# SCH_Desky_2024-12-20.net
KiCad netlist of a schematic drawn in EasyEDA
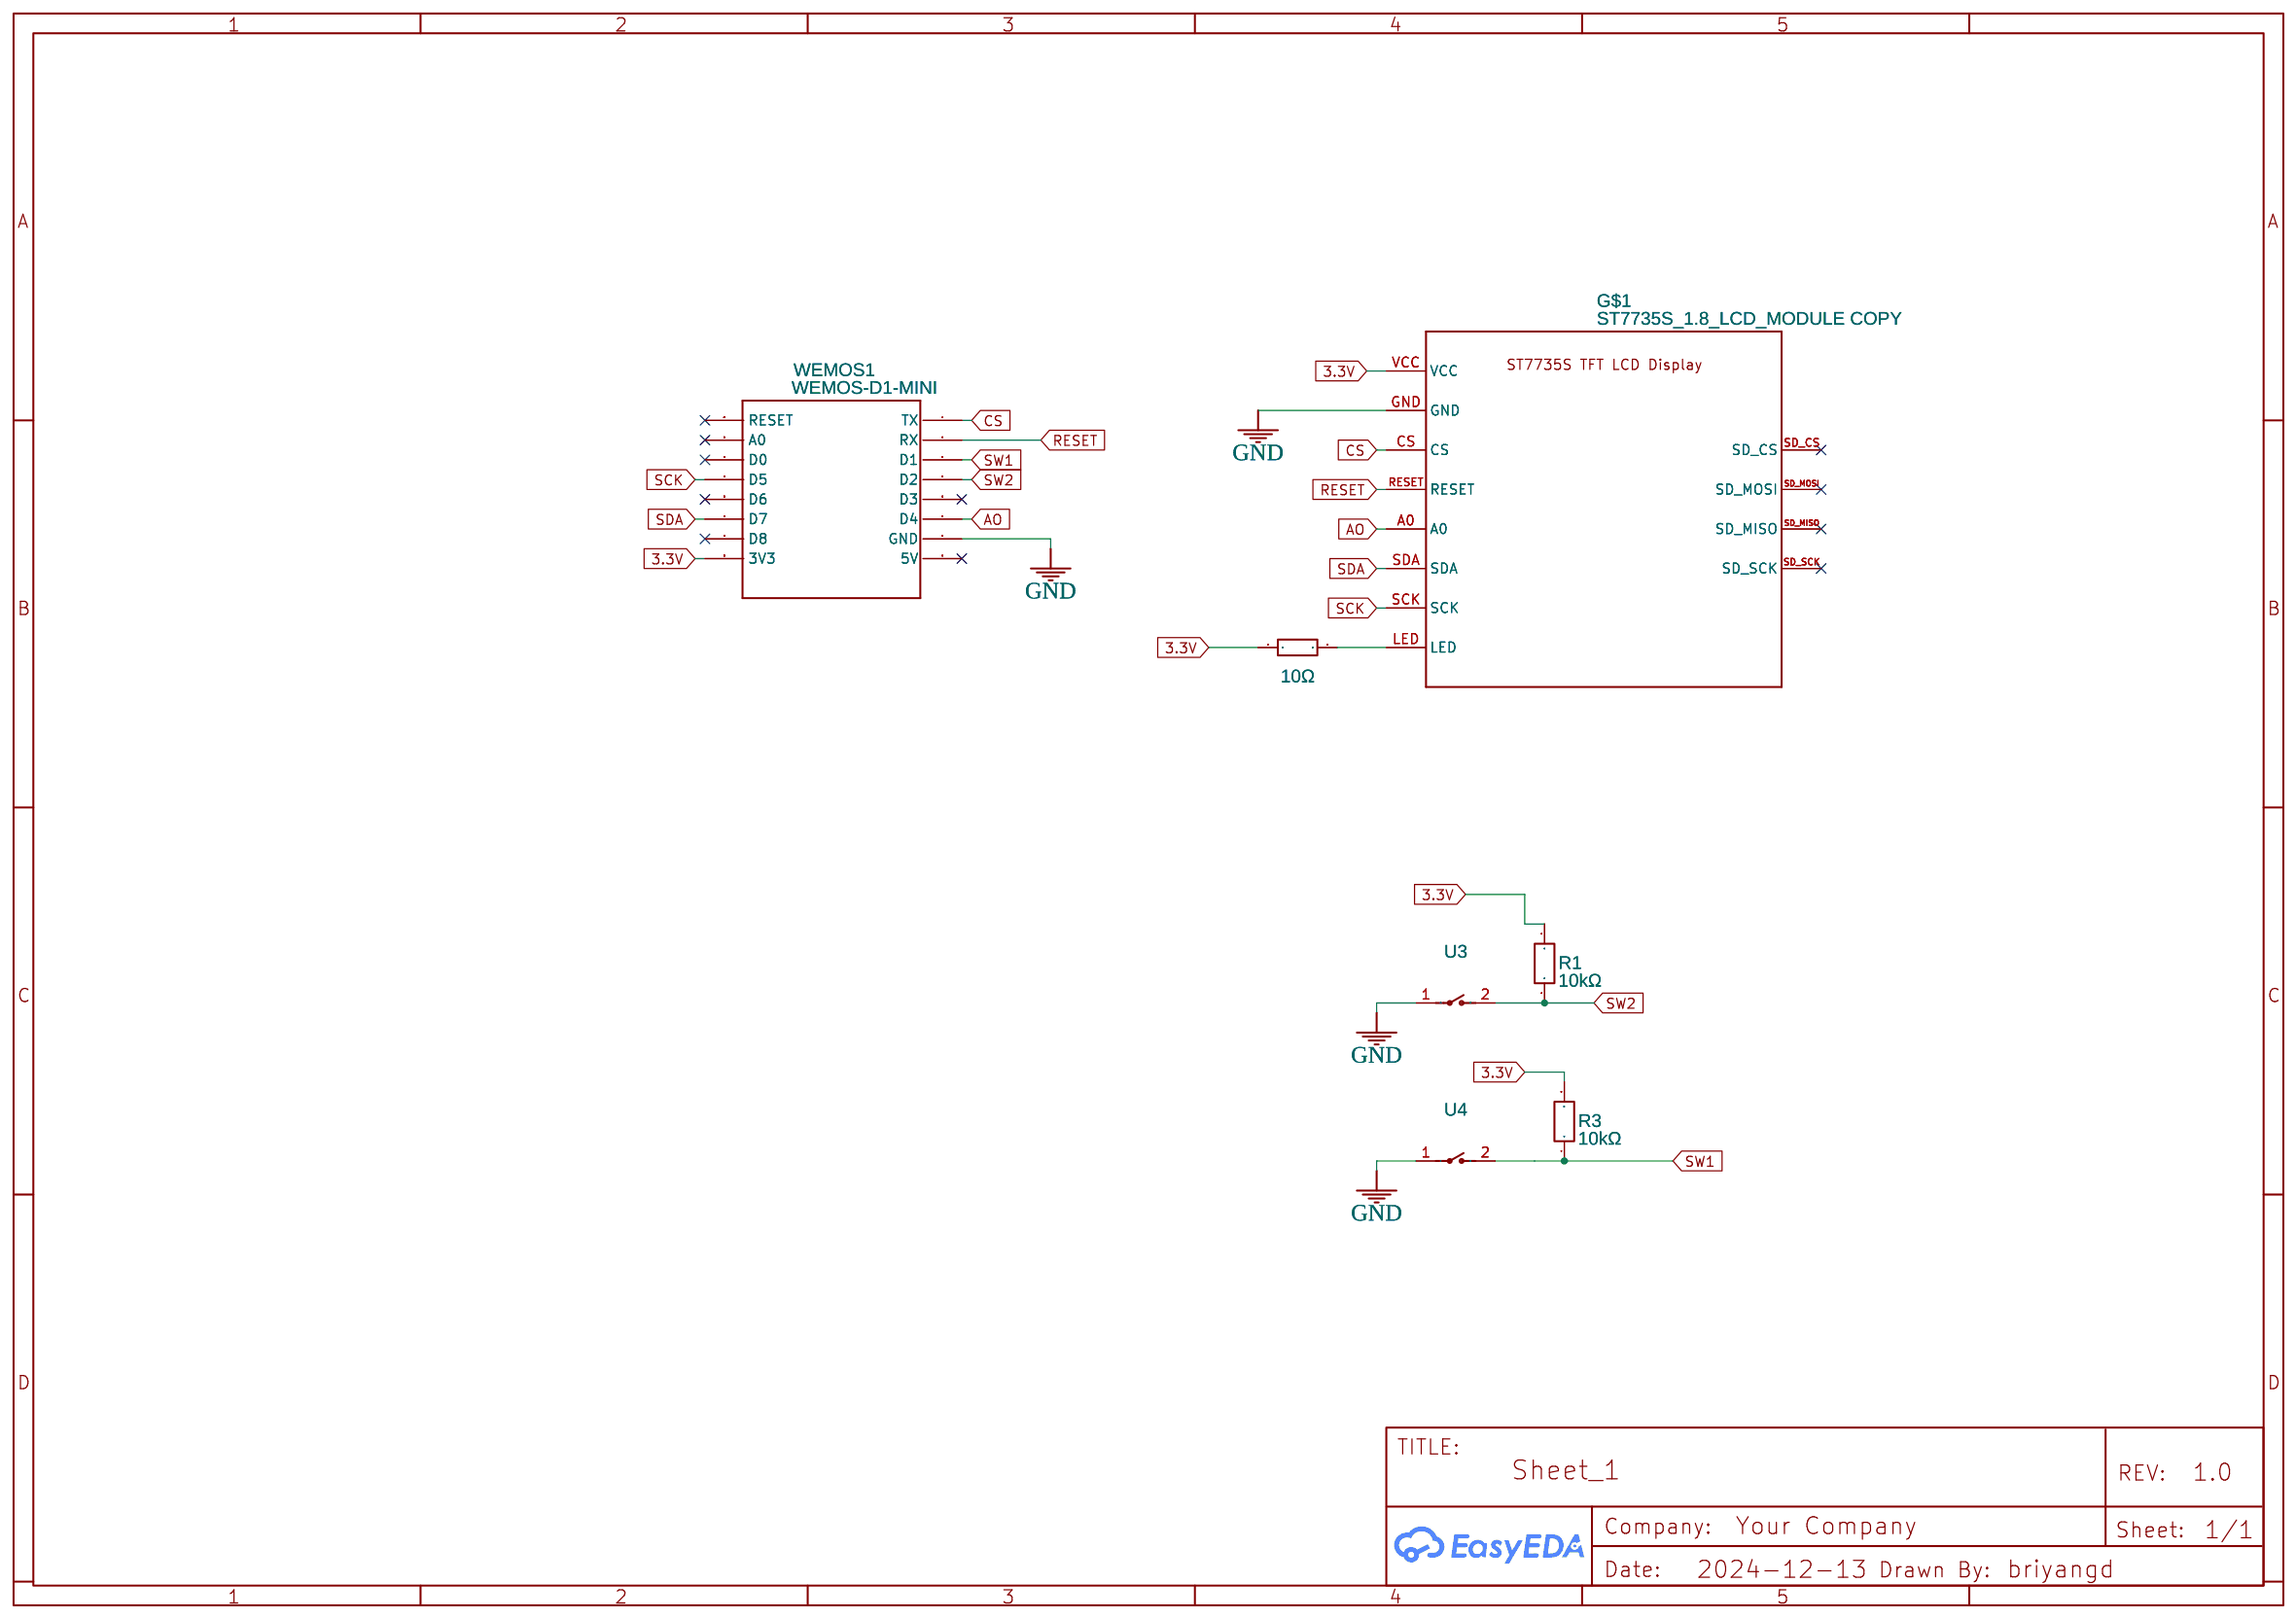
[diagram p0: schematic sheet]

(export (version "E")
  (design (tool "Eeschema 10.0.6"))
  (components
    (comp (ref "G$1")
      (value "ST7735S_1.8_LCD_MODULE COPY")
      (libsource (lib "") (part "ST7735S_1.8_LCD_MODULE COPY"))
    )
    (comp (ref "R1")
      (value "10kΩ")
      (fields
        (field (name "Manufacturer Part") "RN1/4W10KFT/BA1")
        (field (name "Manufacturer") "Tyohm(幸亚电阻)")
      )
      (libsource (lib "") (part "RN 1/4W 10K F T/B A1"))
    )
    (comp (ref "R2")
      (value "10Ω")
      (fields (field (name "Manufacturer Part") "KNP2W-10Ω±5% T") (field (name "Manufacturer") "CCO(千志电子)"))
      (libsource (lib "") (part "KNP2W-10Ω±5% T"))
    )
    (comp (ref "R3")
      (value "10kΩ")
      (fields
        (field (name "Manufacturer Part") "RN1/4W10KFT/BA1")
        (field (name "Manufacturer") "Tyohm(幸亚电阻)")
      )
      (libsource (lib "") (part "RN 1/4W 10K F T/B A1"))
    )
    (comp (ref "U3")
      (value "EVQ-11D05B")
      (fields (field (name "Manufacturer") "PANASONIC(松下)"))
      (libsource (lib "") (part "EVQ-11D05B"))
    )
    (comp (ref "U4")
      (value "EVQ-11D05B")
      (fields (field (name "Manufacturer") "PANASONIC(松下)"))
      (libsource (lib "") (part "EVQ-11D05B"))
    )
    (comp (ref "WEMOS1") (value "WEMOS-D1-MINI") (libsource (lib "") (part "WEMOS-D1-MINI")))
  )
  (nets
    (net (code "1") (name "3.3V") (class "Default")
      (node (ref "G$1") (pin "VCC") (pinfunction "VCC_VCC") (pintype "bidirectional"))
      (node (ref "R1") (pin "2") (pinfunction "2_2") (pintype "unspecified"))
      (node (ref "R2") (pin "1") (pinfunction "1_1") (pintype "unspecified"))
      (node (ref "R3") (pin "2") (pinfunction "2_2") (pintype "unspecified"))
      (node (ref "WEMOS1") (pin "3V3") (pinfunction "3V3_3V3") (pintype "bidirectional"))
    )
    (net (code "2") (name "AO") (class "Default")
      (node (ref "G$1") (pin "A0") (pinfunction "A0_A0") (pintype "bidirectional"))
      (node (ref "WEMOS1") (pin "D4") (pinfunction "D4_D4") (pintype "bidirectional"))
    )
    (net (code "3") (name "CS") (class "Default")
      (node (ref "G$1") (pin "CS") (pinfunction "CS_CS") (pintype "bidirectional"))
      (node (ref "WEMOS1") (pin "TX") (pinfunction "TX_TX") (pintype "bidirectional"))
    )
    (net (code "4") (name "GND") (class "Default")
      (node (ref "G$1") (pin "GND") (pinfunction "GND_GND") (pintype "bidirectional"))
      (node (ref "U3") (pin "1") (pinfunction "1_1") (pintype "unspecified"))
      (node (ref "U4") (pin "1") (pinfunction "1_1") (pintype "unspecified"))
      (node (ref "WEMOS1") (pin "GND") (pinfunction "GND_GND") (pintype "bidirectional"))
    )
    (net (code "5") (name "Net-(G$1-PadLED)") (class "Default")
      (node (ref "G$1") (pin "LED") (pinfunction "LED_LED") (pintype "bidirectional"))
      (node (ref "R2") (pin "2") (pinfunction "2_2") (pintype "unspecified"))
    )
    (net (code "6") (name "RESET") (class "Default")
      (node (ref "G$1") (pin "RESET") (pinfunction "RESET_RESET") (pintype "bidirectional"))
      (node (ref "WEMOS1") (pin "RX") (pinfunction "RX_RX") (pintype "bidirectional"))
    )
    (net (code "7") (name "SCK") (class "Default")
      (node (ref "G$1") (pin "SCK") (pinfunction "SCK_SCK") (pintype "bidirectional"))
      (node (ref "WEMOS1") (pin "D5") (pinfunction "D5_D5") (pintype "bidirectional"))
    )
    (net (code "8") (name "SDA") (class "Default")
      (node (ref "G$1") (pin "SDA") (pinfunction "SDA_SDA") (pintype "bidirectional"))
      (node (ref "WEMOS1") (pin "D7") (pinfunction "D7_D7") (pintype "bidirectional"))
    )
    (net (code "9") (name "SW1") (class "Default")
      (node (ref "R3") (pin "1") (pinfunction "1_1") (pintype "unspecified"))
      (node (ref "U4") (pin "2") (pinfunction "2_2") (pintype "unspecified"))
      (node (ref "WEMOS1") (pin "D1") (pinfunction "D1_D1") (pintype "bidirectional"))
    )
    (net (code "10") (name "SW2") (class "Default")
      (node (ref "R1") (pin "1") (pinfunction "1_1") (pintype "unspecified"))
      (node (ref "U3") (pin "2") (pinfunction "2_2") (pintype "unspecified"))
      (node (ref "WEMOS1") (pin "D2") (pinfunction "D2_D2") (pintype "bidirectional"))
    )
    (net (code "11") (name "unconnected-(G$1-PadSD_CS)") (class "Default")
      (node (ref "G$1") (pin "SD_CS") (pinfunction "SD_CS_SD_CS") (pintype "bidirectional+no_connect"))
    )
    (net (code "12") (name "unconnected-(G$1-PadSD_MISO)") (class "Default")
      (node (ref "G$1") (pin "SD_MISO") (pinfunction "SD_MISO_SD_MISO") (pintype "bidirectional+no_connect"))
    )
    (net (code "13") (name "unconnected-(G$1-PadSD_MOSI)") (class "Default")
      (node (ref "G$1") (pin "SD_MOSI") (pinfunction "SD_MOSI_SD_MOSI") (pintype "bidirectional+no_connect"))
    )
    (net (code "14") (name "unconnected-(G$1-PadSD_SCK)") (class "Default")
      (node (ref "G$1") (pin "SD_SCK") (pinfunction "SD_SCK_SD_SCK") (pintype "bidirectional+no_connect"))
    )
    (net (code "15") (name "unconnected-(WEMOS1-Pad5V)") (class "Default")
      (node (ref "WEMOS1") (pin "5V") (pinfunction "5V_5V") (pintype "bidirectional+no_connect"))
    )
    (net (code "16") (name "unconnected-(WEMOS1-PadA0)") (class "Default")
      (node (ref "WEMOS1") (pin "A0") (pinfunction "A0_A0") (pintype "bidirectional+no_connect"))
    )
    (net (code "17") (name "unconnected-(WEMOS1-PadD0)") (class "Default")
      (node (ref "WEMOS1") (pin "D0") (pinfunction "D0_D0") (pintype "bidirectional+no_connect"))
    )
    (net (code "18") (name "unconnected-(WEMOS1-PadD3)") (class "Default")
      (node (ref "WEMOS1") (pin "D3") (pinfunction "D3_D3") (pintype "bidirectional+no_connect"))
    )
    (net (code "19") (name "unconnected-(WEMOS1-PadD6)") (class "Default")
      (node (ref "WEMOS1") (pin "D6") (pinfunction "D6_D6") (pintype "bidirectional+no_connect"))
    )
    (net (code "20") (name "unconnected-(WEMOS1-PadD8)") (class "Default")
      (node (ref "WEMOS1") (pin "D8") (pinfunction "D8_D8") (pintype "bidirectional+no_connect"))
    )
    (net (code "21") (name "unconnected-(WEMOS1-PadRESET)") (class "Default")
      (node (ref "WEMOS1") (pin "RESET") (pinfunction "RESET_RESET") (pintype "bidirectional+no_connect"))
    )
  )
)
